# MOSFET_Switch_Parallel.net
KiCad netlist of a schematic drawn in Altium Designer
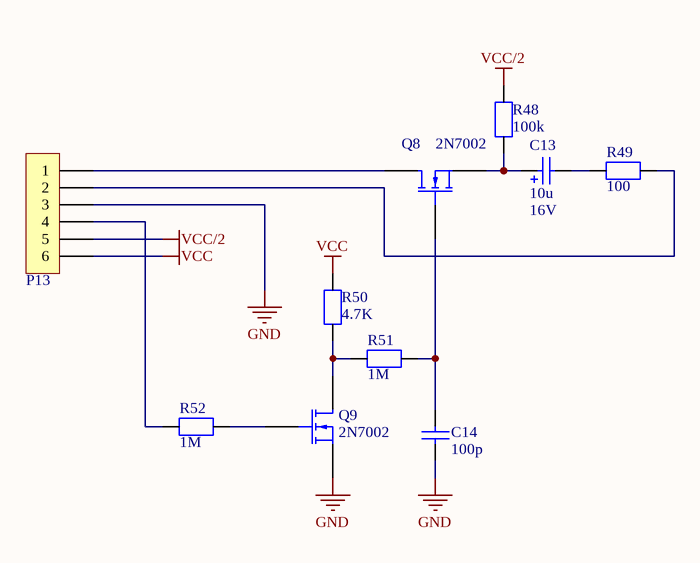
[diagram p0: MOSFET_Switch_Parallel.SchDoc]

(export (version "E")
  (design (tool "Eeschema 10.0.6"))
  (components
    (comp (ref "C13")
      (value "10u")
      (footprint "ELEC_RAD10")
      (fields (field (name "INITIAL VOLTAGE") "16V") (field (name "Comment") "Electrolytic Capacitor"))
      (libsource (lib "SchLib1") (part "Electrolytic Capacitor"))
    )
    (comp (ref "C14")
      (value "100p")
      (footprint "0805_Capacitor")
      (fields (field (name "Comment") "Capacitor"))
      (libsource (lib "SchLib1") (part "Capacitor"))
    )
    (comp (ref "P13")
      (value "SIL-CONN-6")
      (footprint "SIL-CONN-6-R2")
      (libsource (lib "SchLib1") (part "SIL-CONN-6"))
    )
    (comp (ref "Q8") (value "2N7002") (footprint "SOT23-3") (libsource (lib "SchLib1") (part "2N7002")))
    (comp (ref "Q9") (value "2N7002") (footprint "SOT23-3") (libsource (lib "SchLib1") (part "2N7002")))
    (comp (ref "R48")
      (value "100k")
      (footprint "0805_Resistor")
      (fields (field (name "Comment") "Resistor"))
      (libsource (lib "") (part "Resistor_1"))
    )
    (comp (ref "R49")
      (value "100")
      (footprint "0805_Resistor")
      (fields (field (name "Comment") "Resistor"))
      (libsource (lib "SchLib1") (part "Resistor"))
    )
    (comp (ref "R50")
      (value "4.7K")
      (footprint "0805_Resistor")
      (fields (field (name "Comment") "Resistor"))
      (libsource (lib "SchLib1") (part "Resistor"))
    )
    (comp (ref "R51")
      (value "1M")
      (footprint "0805_Resistor")
      (fields (field (name "Comment") "Resistor"))
      (libsource (lib "SchLib1") (part "Resistor"))
    )
    (comp (ref "R52")
      (value "1M")
      (footprint "0805_Resistor")
      (fields (field (name "Comment") "Resistor"))
      (libsource (lib "") (part "Resistor_2"))
    )
  )
  (nets
    (net (code "1") (name "GND") (class "Default")
      (node (ref "C14") (pin "1") (pinfunction "1_1") (pintype "passive"))
      (node (ref "P13") (pin "3") (pinfunction "3_3") (pintype "passive"))
      (node (ref "Q9") (pin "S") (pinfunction "S_S") (pintype "passive"))
    )
    (net (code "2") (name "Net-(C13-Pad+)") (class "Default")
      (node (ref "C13") (pin "+") (pinfunction "+_+") (pintype "passive"))
      (node (ref "Q8") (pin "S") (pinfunction "S_S") (pintype "passive"))
      (node (ref "R48") (pin "1") (pinfunction "1_1") (pintype "passive"))
    )
    (net (code "3") (name "Net-(C13-Pad-)") (class "Default")
      (node (ref "C13") (pin "-") (pinfunction "-_-") (pintype "passive"))
      (node (ref "R49") (pin "1") (pinfunction "1_1") (pintype "passive"))
    )
    (net (code "4") (name "Net-(C14-Pad2)") (class "Default")
      (node (ref "C14") (pin "2") (pinfunction "2_2") (pintype "passive"))
      (node (ref "Q8") (pin "G") (pinfunction "G_G") (pintype "passive"))
      (node (ref "R51") (pin "2") (pinfunction "2_2") (pintype "passive"))
    )
    (net (code "5") (name "Net-(P13-Pad1)") (class "Default")
      (node (ref "P13") (pin "1") (pinfunction "1_1") (pintype "passive"))
      (node (ref "Q8") (pin "D") (pinfunction "D_D") (pintype "passive"))
    )
    (net (code "6") (name "Net-(P13-Pad2)") (class "Default")
      (node (ref "P13") (pin "2") (pinfunction "2_2") (pintype "passive"))
      (node (ref "R49") (pin "2") (pinfunction "2_2") (pintype "passive"))
    )
    (net (code "7") (name "Net-(P13-Pad4)") (class "Default")
      (node (ref "P13") (pin "4") (pinfunction "4_4") (pintype "passive"))
      (node (ref "R52") (pin "2") (pinfunction "2_2") (pintype "passive"))
    )
    (net (code "8") (name "Net-(Q9-PadD)") (class "Default")
      (node (ref "Q9") (pin "D") (pinfunction "D_D") (pintype "passive"))
      (node (ref "R50") (pin "1") (pinfunction "1_1") (pintype "passive"))
      (node (ref "R51") (pin "1") (pinfunction "1_1") (pintype "passive"))
    )
    (net (code "9") (name "Net-(Q9-PadG)") (class "Default")
      (node (ref "Q9") (pin "G") (pinfunction "G_G") (pintype "passive"))
      (node (ref "R52") (pin "1") (pinfunction "1_1") (pintype "passive"))
    )
    (net (code "10") (name "VCC") (class "Default")
      (node (ref "P13") (pin "6") (pinfunction "6_6") (pintype "passive"))
      (node (ref "R50") (pin "2") (pinfunction "2_2") (pintype "passive"))
    )
    (net (code "11") (name "VCC{slash}2") (class "Default")
      (node (ref "P13") (pin "5") (pinfunction "5_5") (pintype "passive"))
      (node (ref "R48") (pin "2") (pinfunction "2_2") (pintype "passive"))
    )
  )
)
